# PIR_Shield.net
KiCad netlist of a schematic drawn in EAGLE
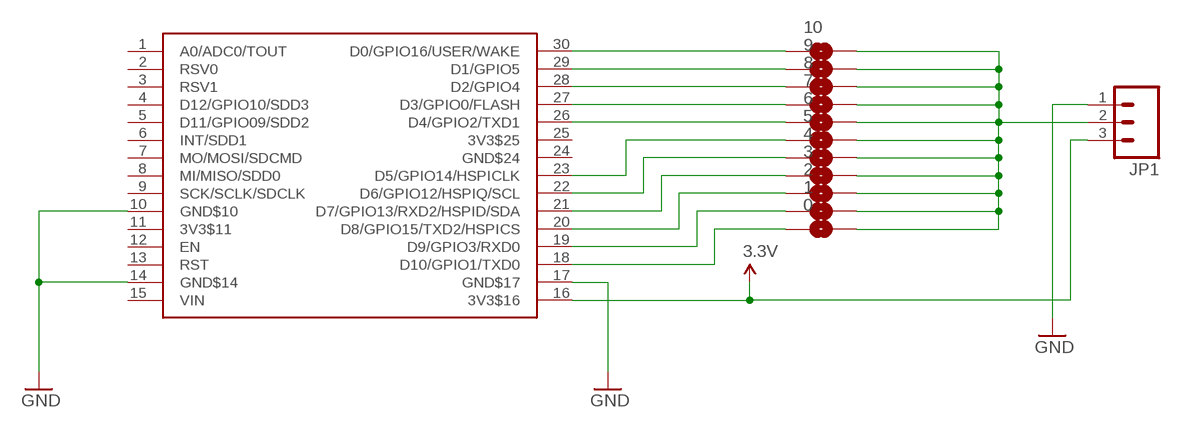
[diagram p0: schematic, sheet 1]

(export (version "E")
  (design (tool "Eeschema 10.0.6"))
  (components
    (comp (ref "0")
      (value "SOLDERJUMPERNO")
      (footprint "eagle-import:SJ_2S-NO")
      (libsource (lib "eagle-import") (part "SOLDERJUMPERNO"))
    )
    (comp (ref "1")
      (value "SOLDERJUMPERNO")
      (footprint "eagle-import:SJ_2S-NO")
      (libsource (lib "eagle-import") (part "SOLDERJUMPERNO"))
    )
    (comp (ref "2")
      (value "SOLDERJUMPERNO")
      (footprint "eagle-import:SJ_2S-NO")
      (libsource (lib "eagle-import") (part "SOLDERJUMPERNO"))
    )
    (comp (ref "3")
      (value "SOLDERJUMPERNO")
      (footprint "eagle-import:SJ_2S-NO")
      (libsource (lib "eagle-import") (part "SOLDERJUMPERNO"))
    )
    (comp (ref "4")
      (value "SOLDERJUMPERNO")
      (footprint "eagle-import:SJ_2S-NO")
      (libsource (lib "eagle-import") (part "SOLDERJUMPERNO"))
    )
    (comp (ref "5")
      (value "SOLDERJUMPERNO")
      (footprint "eagle-import:SJ_2S-NO")
      (libsource (lib "eagle-import") (part "SOLDERJUMPERNO"))
    )
    (comp (ref "6")
      (value "SOLDERJUMPERNO")
      (footprint "eagle-import:SJ_2S-NO")
      (libsource (lib "eagle-import") (part "SOLDERJUMPERNO"))
    )
    (comp (ref "7")
      (value "SOLDERJUMPERNO")
      (footprint "eagle-import:SJ_2S-NO")
      (libsource (lib "eagle-import") (part "SOLDERJUMPERNO"))
    )
    (comp (ref "8")
      (value "SOLDERJUMPERNO")
      (footprint "eagle-import:SJ_2S-NO")
      (libsource (lib "eagle-import") (part "SOLDERJUMPERNO"))
    )
    (comp (ref "9")
      (value "SOLDERJUMPERNO")
      (footprint "eagle-import:SJ_2S-NO")
      (libsource (lib "eagle-import") (part "SOLDERJUMPERNO"))
    )
    (comp (ref "10")
      (value "SOLDERJUMPERNC")
      (footprint "eagle-import:SJ_2S")
      (libsource (lib "eagle-import") (part "SOLDERJUMPERNC"))
    )
    (comp (ref "JP1")
      (value "M03PTH")
      (footprint "eagle-import:1X03")
      (libsource (lib "eagle-import") (part "M03PTH"))
    )
    (comp (ref "U$1")
      (value "NERDSHIELD")
      (footprint "eagle-import:NERDUINO_STACK")
      (libsource (lib "eagle-import") (part "NERDSHIELD"))
    )
  )
  (nets
    (net (code "1") (name "3.3V") (class "Default")
      (node (ref "JP1") (pin "3") (pinfunction "3_3") (pintype "passive"))
      (node (ref "U$1") (pin "16") (pinfunction "3V3$16_16") (pintype "bidirectional"))
    )
    (net (code "2") (name "GND") (class "Default")
      (node (ref "JP1") (pin "1") (pinfunction "1_1") (pintype "passive"))
      (node (ref "U$1") (pin "10") (pinfunction "GND$10_10") (pintype "bidirectional"))
      (node (ref "U$1") (pin "14") (pinfunction "GND$14_14") (pintype "bidirectional"))
      (node (ref "U$1") (pin "17") (pinfunction "GND$17_17") (pintype "bidirectional"))
    )
    (net (code "3") (name "Net-(0-Pad2)") (class "Default")
      (node (ref "0") (pin "2") (pinfunction "2_2") (pintype "passive"))
      (node (ref "1") (pin "2") (pinfunction "2_2") (pintype "passive"))
      (node (ref "10") (pin "2") (pinfunction "2_2") (pintype "passive"))
      (node (ref "2") (pin "2") (pinfunction "2_2") (pintype "passive"))
      (node (ref "3") (pin "2") (pinfunction "2_2") (pintype "passive"))
      (node (ref "4") (pin "2") (pinfunction "2_2") (pintype "passive"))
      (node (ref "5") (pin "2") (pinfunction "2_2") (pintype "passive"))
      (node (ref "6") (pin "2") (pinfunction "2_2") (pintype "passive"))
      (node (ref "7") (pin "2") (pinfunction "2_2") (pintype "passive"))
      (node (ref "8") (pin "2") (pinfunction "2_2") (pintype "passive"))
      (node (ref "9") (pin "2") (pinfunction "2_2") (pintype "passive"))
      (node (ref "JP1") (pin "2") (pinfunction "2_2") (pintype "passive"))
    )
    (net (code "4") (name "Net-(U$1-D0{slash}GPIO16{slash}USER{slash}WAKE)") (class "Default")
      (node (ref "10") (pin "1") (pinfunction "1_1") (pintype "passive"))
      (node (ref "U$1") (pin "30") (pinfunction "D0/GPIO16/USER/WAKE_30") (pintype "bidirectional"))
    )
    (net (code "5") (name "Net-(U$1-D1{slash}GPIO5)") (class "Default")
      (node (ref "9") (pin "1") (pinfunction "1_1") (pintype "passive"))
      (node (ref "U$1") (pin "29") (pinfunction "D1/GPIO5_29") (pintype "bidirectional"))
    )
    (net (code "6") (name "Net-(U$1-D2{slash}GPIO4)") (class "Default")
      (node (ref "8") (pin "1") (pinfunction "1_1") (pintype "passive"))
      (node (ref "U$1") (pin "28") (pinfunction "D2/GPIO4_28") (pintype "bidirectional"))
    )
    (net (code "7") (name "Net-(U$1-D3{slash}GPIO0{slash}FLASH)") (class "Default")
      (node (ref "7") (pin "1") (pinfunction "1_1") (pintype "passive"))
      (node (ref "U$1") (pin "27") (pinfunction "D3/GPIO0/FLASH_27") (pintype "bidirectional"))
    )
    (net (code "8") (name "Net-(U$1-D4{slash}GPIO2{slash}TXD1)") (class "Default")
      (node (ref "6") (pin "1") (pinfunction "1_1") (pintype "passive"))
      (node (ref "U$1") (pin "26") (pinfunction "D4/GPIO2/TXD1_26") (pintype "bidirectional"))
    )
    (net (code "9") (name "Net-(U$1-D5{slash}GPIO14{slash}HSPICLK)") (class "Default")
      (node (ref "5") (pin "1") (pinfunction "1_1") (pintype "passive"))
      (node (ref "U$1") (pin "23") (pinfunction "D5/GPIO14/HSPICLK_23") (pintype "bidirectional"))
    )
    (net (code "10") (name "Net-(U$1-D6{slash}GPIO12{slash}HSPIQ{slash}SCL)") (class "Default")
      (node (ref "4") (pin "1") (pinfunction "1_1") (pintype "passive"))
      (node (ref "U$1") (pin "22") (pinfunction "D6/GPIO12/HSPIQ/SCL_22") (pintype "bidirectional"))
    )
    (net (code "11") (name "Net-(U$1-D7{slash}GPIO13{slash}RXD2{slash}HSPID{slash}SDA)") (class "Default")
      (node (ref "3") (pin "1") (pinfunction "1_1") (pintype "passive"))
      (node (ref "U$1") (pin "21") (pinfunction "D7/GPIO13/RXD2/HSPID/SDA_21") (pintype "bidirectional"))
    )
    (net (code "12") (name "Net-(U$1-D8{slash}GPIO15{slash}TXD2{slash}HSPICS)") (class "Default")
      (node (ref "2") (pin "1") (pinfunction "1_1") (pintype "passive"))
      (node (ref "U$1") (pin "20") (pinfunction "D8/GPIO15/TXD2/HSPICS_20") (pintype "bidirectional"))
    )
    (net (code "13") (name "Net-(U$1-D9{slash}GPIO3{slash}RXD0)") (class "Default")
      (node (ref "1") (pin "1") (pinfunction "1_1") (pintype "passive"))
      (node (ref "U$1") (pin "19") (pinfunction "D9/GPIO3/RXD0_19") (pintype "bidirectional"))
    )
    (net (code "14") (name "Net-(U$1-D10{slash}GPIO1{slash}TXD0)") (class "Default")
      (node (ref "0") (pin "1") (pinfunction "1_1") (pintype "passive"))
      (node (ref "U$1") (pin "18") (pinfunction "D10/GPIO1/TXD0_18") (pintype "bidirectional"))
    )
    (net (code "15") (name "unconnected-(U$1-3V3$11-Pad11)") (class "Default")
      (node (ref "U$1") (pin "11") (pinfunction "3V3$11_11") (pintype "bidirectional"))
    )
    (net (code "16") (name "unconnected-(U$1-3V3$25-Pad25)") (class "Default")
      (node (ref "U$1") (pin "25") (pinfunction "3V3$25_25") (pintype "bidirectional"))
    )
    (net (code "17") (name "unconnected-(U$1-A0{slash}ADC0{slash}TOUT-Pad1)") (class "Default")
      (node (ref "U$1") (pin "1") (pinfunction "A0/ADC0/TOUT_1") (pintype "bidirectional"))
    )
    (net (code "18") (name "unconnected-(U$1-D11{slash}GPIO09{slash}SDD2-Pad5)") (class "Default")
      (node (ref "U$1") (pin "5") (pinfunction "D11/GPIO09/SDD2_5") (pintype "bidirectional"))
    )
    (net (code "19") (name "unconnected-(U$1-D12{slash}GPIO10{slash}SDD3-Pad4)") (class "Default")
      (node (ref "U$1") (pin "4") (pinfunction "D12/GPIO10/SDD3_4") (pintype "bidirectional"))
    )
    (net (code "20") (name "unconnected-(U$1-EN-Pad12)") (class "Default")
      (node (ref "U$1") (pin "12") (pinfunction "EN_12") (pintype "bidirectional"))
    )
    (net (code "21") (name "unconnected-(U$1-GND$24-Pad24)") (class "Default")
      (node (ref "U$1") (pin "24") (pinfunction "GND$24_24") (pintype "bidirectional"))
    )
    (net (code "22") (name "unconnected-(U$1-INT{slash}SDD1-Pad6)") (class "Default")
      (node (ref "U$1") (pin "6") (pinfunction "INT/SDD1_6") (pintype "bidirectional"))
    )
    (net (code "23") (name "unconnected-(U$1-MI{slash}MISO{slash}SDD0-Pad8)") (class "Default")
      (node (ref "U$1") (pin "8") (pinfunction "MI/MISO/SDD0_8") (pintype "bidirectional"))
    )
    (net (code "24") (name "unconnected-(U$1-MO{slash}MOSI{slash}SDCMD-Pad7)") (class "Default")
      (node (ref "U$1") (pin "7") (pinfunction "MO/MOSI/SDCMD_7") (pintype "bidirectional"))
    )
    (net (code "25") (name "unconnected-(U$1-RST-Pad13)") (class "Default")
      (node (ref "U$1") (pin "13") (pinfunction "RST_13") (pintype "bidirectional"))
    )
    (net (code "26") (name "unconnected-(U$1-RSV0-Pad2)") (class "Default")
      (node (ref "U$1") (pin "2") (pinfunction "RSV0_2") (pintype "bidirectional"))
    )
    (net (code "27") (name "unconnected-(U$1-RSV1-Pad3)") (class "Default")
      (node (ref "U$1") (pin "3") (pinfunction "RSV1_3") (pintype "bidirectional"))
    )
    (net (code "28") (name "unconnected-(U$1-SCK{slash}SCLK{slash}SDCLK-Pad9)") (class "Default")
      (node (ref "U$1") (pin "9") (pinfunction "SCK/SCLK/SDCLK_9") (pintype "bidirectional"))
    )
    (net (code "29") (name "unconnected-(U$1-VIN-Pad15)") (class "Default")
      (node (ref "U$1") (pin "15") (pinfunction "VIN_15") (pintype "bidirectional"))
    )
  )
)
